# AFE_DIFF.net
KiCad netlist of a schematic drawn in Altium Designer
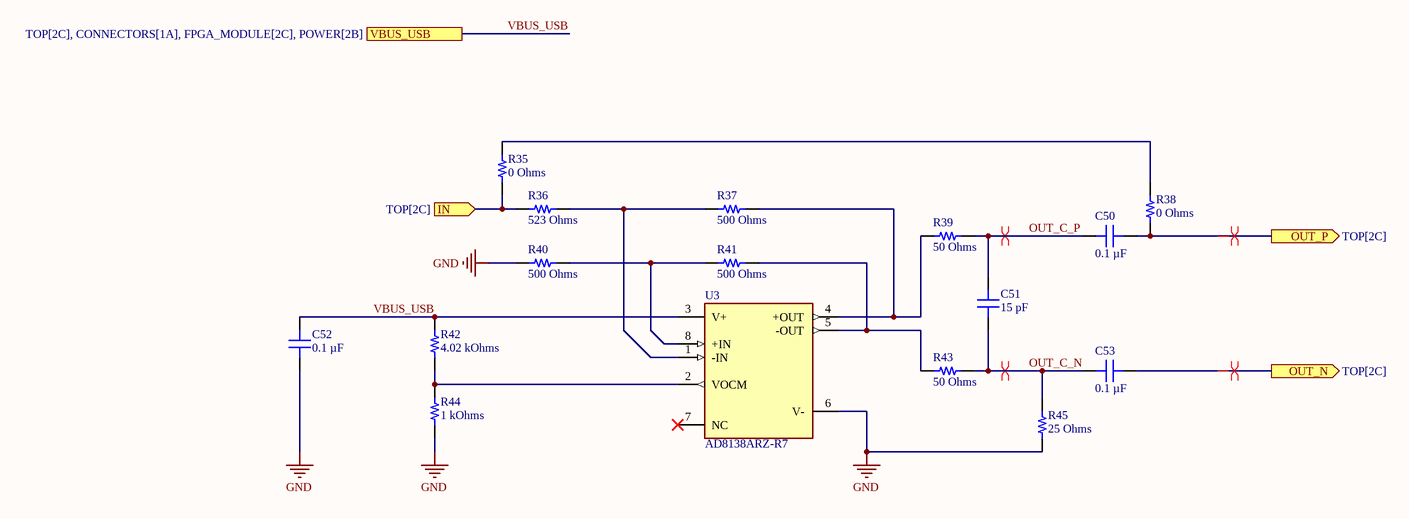
[diagram p0: AFE_DIFF.SchDoc]

(export (version "E")
  (design (tool "Eeschema 10.0.6"))
  (components
    (comp (ref "C50")
      (value "0.1 µF")
      (footprint "CAP 0402_1005")
      (description "CAP CER 0.1UF 50V X5R 0402")
      (fields
        (field (name "PART NUMBER") "CGA2B3X5R1H104M050BB")
        (field (name "MANUFACTURER") "TDK Corporation")
      )
      (libsource (lib "Celestial") (part "Capacitor"))
    )
    (comp (ref "C51")
      (value "15 pF")
      (footprint "CAP 0603_1608")
      (description "CAP CER 15PF 25V C0G/NP0 0603")
      (fields (field (name "PART NUMBER") "C0603C150J3GACAUTO") (field (name "MANUFACTURER") "KEMET"))
      (libsource (lib "Celestial") (part "Capacitor"))
    )
    (comp (ref "C52")
      (value "0.1 µF")
      (footprint "CAP 0402_1005")
      (description "CAP CER 0.1UF 50V X5R 0402")
      (fields
        (field (name "PART NUMBER") "CGA2B3X5R1H104M050BB")
        (field (name "MANUFACTURER") "TDK Corporation")
      )
      (libsource (lib "Celestial") (part "Capacitor"))
    )
    (comp (ref "C53")
      (value "0.1 µF")
      (footprint "CAP 0402_1005")
      (description "CAP CER 0.1UF 50V X5R 0402")
      (fields
        (field (name "PART NUMBER") "CGA2B3X5R1H104M050BB")
        (field (name "MANUFACTURER") "TDK Corporation")
      )
      (libsource (lib "Celestial") (part "Capacitor"))
    )
    (comp (ref "R35")
      (value "0 Ohms")
      (footprint "RES 0603_1608")
      (description "RES SMD 0 OHM JUMPER 1/2W 0603")
      (fields (field (name "PART NUMBER") "5110") (field (name "MANUFACTURER") "Keystone Electronics"))
      (libsource (lib "Celestial") (part "Resistor"))
    )
    (comp (ref "R36")
      (value "523 Ohms")
      (footprint "RES 0402_1005")
      (description "RES SMD 523 OHM 0.1% 1/16W 0402")
      (fields
        (field (name "PART NUMBER") "ERA-2ARB5230X")
        (field (name "MANUFACTURER") "Panasonic Electronic Components")
      )
      (libsource (lib "Celestial") (part "Resistor"))
    )
    (comp (ref "R37")
      (value "500 Ohms")
      (footprint "RES 0603_1608")
      (description "RES SMD 500 OHM 0.05% 1/10W 0603")
      (fields (field (name "PART NUMBER") "TNPU0603500RAZEN00") (field (name "MANUFACTURER") "Vishay Dale"))
      (libsource (lib "Celestial") (part "Resistor"))
    )
    (comp (ref "R38")
      (value "0 Ohms")
      (footprint "RES 0603_1608")
      (description "RES SMD 0 OHM JUMPER 1/2W 0603")
      (fields (field (name "PART NUMBER") "5110") (field (name "MANUFACTURER") "Keystone Electronics"))
      (libsource (lib "Celestial") (part "Resistor"))
    )
    (comp (ref "R39")
      (value "50 Ohms")
      (footprint "RES 0603_1608")
      (description "RES 50 OHM 5% 1/8W 0603")
      (fields (field (name "PART NUMBER") "CH0603-50RJNTA") (field (name "MANUFACTURER") "Vishay Sfernice"))
      (libsource (lib "Celestial") (part "Resistor"))
    )
    (comp (ref "R40")
      (value "500 Ohms")
      (footprint "RES 0603_1608")
      (description "RES SMD 500 OHM 0.05% 1/10W 0603")
      (fields (field (name "PART NUMBER") "TNPU0603500RAZEN00") (field (name "MANUFACTURER") "Vishay Dale"))
      (libsource (lib "Celestial") (part "Resistor"))
    )
    (comp (ref "R41")
      (value "500 Ohms")
      (footprint "RES 0603_1608")
      (description "RES SMD 500 OHM 0.05% 1/10W 0603")
      (fields (field (name "PART NUMBER") "TNPU0603500RAZEN00") (field (name "MANUFACTURER") "Vishay Dale"))
      (libsource (lib "Celestial") (part "Resistor"))
    )
    (comp (ref "R42")
      (value "4.02 kOhms")
      (footprint "RES 0603_1608")
      (description "RES SMD 4.02K OHM 1% 1/10W 0603")
      (fields (field (name "PART NUMBER") "AC0603FR-074K02L") (field (name "MANUFACTURER") "Yageo"))
      (libsource (lib "Celestial") (part "Resistor"))
    )
    (comp (ref "R43")
      (value "50 Ohms")
      (footprint "RES 0603_1608")
      (description "RES 50 OHM 5% 1/8W 0603")
      (fields (field (name "PART NUMBER") "CH0603-50RJNTA") (field (name "MANUFACTURER") "Vishay Sfernice"))
      (libsource (lib "Celestial") (part "Resistor"))
    )
    (comp (ref "R44")
      (value "1 kOhms")
      (footprint "RES 0603_1608")
      (description "RES SMD 1K OHM 1% 1/10W 0603")
      (fields (field (name "PART NUMBER") "AA0603FR-071KL") (field (name "MANUFACTURER") "Yageo"))
      (libsource (lib "Celestial") (part "Resistor"))
    )
    (comp (ref "R45")
      (value "25 Ohms")
      (footprint "RES 0402_1005")
      (description "RES 25 OHM 0.1% 1/20W 0402")
      (fields (field (name "PART NUMBER") "FC0402E25R0BST0") (field (name "MANUFACTURER") "Vishay Thin Film"))
      (libsource (lib "Celestial") (part "Resistor"))
    )
    (comp (ref "U3")
      (value "AD8138ARZ-R7")
      (footprint "FP-R-8-IPC_A")
      (description "IC ADC DRIVER 8SOIC")
      (libsource (lib "Altium Content Vault") (part "538c1b5816b8d819c8aa865c7aeb83c"))
    )
  )
  (nets
    (net (code "1") (name "/IN") (class "Default")
      (node (ref "R35") (pin "1") (pinfunction "1_1") (pintype "passive"))
      (node (ref "R36") (pin "1") (pinfunction "1_1") (pintype "passive"))
    )
    (net (code "2") (name "/OUT_C_N") (class "Default")
      (node (ref "C51") (pin "1") (pinfunction "1_1") (pintype "passive"))
      (node (ref "C53") (pin "2") (pinfunction "2_2") (pintype "passive"))
      (node (ref "R43") (pin "2") (pinfunction "2_2") (pintype "passive"))
      (node (ref "R45") (pin "2") (pinfunction "2_2") (pintype "passive"))
    )
    (net (code "3") (name "/OUT_C_P") (class "Default")
      (node (ref "C50") (pin "2") (pinfunction "2_2") (pintype "passive"))
      (node (ref "C51") (pin "2") (pinfunction "2_2") (pintype "passive"))
      (node (ref "R39") (pin "2") (pinfunction "2_2") (pintype "passive"))
    )
    (net (code "4") (name "/OUT_N") (class "Default")
      (node (ref "C53") (pin "1") (pinfunction "1_1") (pintype "passive"))
    )
    (net (code "5") (name "/OUT_P") (class "Default")
      (node (ref "C50") (pin "1") (pinfunction "1_1") (pintype "passive"))
      (node (ref "R38") (pin "1") (pinfunction "1_1") (pintype "passive"))
    )
    (net (code "6") (name "/VBUS_USB") (class "Default")
      (node (ref "C52") (pin "2") (pinfunction "2_2") (pintype "passive"))
      (node (ref "R42") (pin "2") (pinfunction "2_2") (pintype "passive"))
      (node (ref "U3") (pin "3") (pinfunction "V+_3") (pintype "power_in"))
    )
    (net (code "7") (name "GND") (class "Default")
      (node (ref "C52") (pin "1") (pinfunction "1_1") (pintype "passive"))
      (node (ref "R40") (pin "1") (pinfunction "1_1") (pintype "passive"))
      (node (ref "R44") (pin "1") (pinfunction "1_1") (pintype "passive"))
      (node (ref "R45") (pin "1") (pinfunction "1_1") (pintype "passive"))
      (node (ref "U3") (pin "6") (pinfunction "V-_6") (pintype "power_in"))
    )
    (net (code "8") (name "Net-(R35-Pad2)") (class "Default")
      (node (ref "R35") (pin "2") (pinfunction "2_2") (pintype "passive"))
      (node (ref "R38") (pin "2") (pinfunction "2_2") (pintype "passive"))
    )
    (net (code "9") (name "Net-(U3-+IN)") (class "Default")
      (node (ref "R40") (pin "2") (pinfunction "2_2") (pintype "passive"))
      (node (ref "R41") (pin "1") (pinfunction "1_1") (pintype "passive"))
      (node (ref "U3") (pin "8") (pinfunction "+IN_8") (pintype "input"))
    )
    (net (code "10") (name "Net-(U3-+OUT)") (class "Default")
      (node (ref "R37") (pin "2") (pinfunction "2_2") (pintype "passive"))
      (node (ref "R39") (pin "1") (pinfunction "1_1") (pintype "passive"))
      (node (ref "U3") (pin "4") (pinfunction "+OUT_4") (pintype "output"))
    )
    (net (code "11") (name "Net-(U3--IN)") (class "Default")
      (node (ref "R36") (pin "2") (pinfunction "2_2") (pintype "passive"))
      (node (ref "R37") (pin "1") (pinfunction "1_1") (pintype "passive"))
      (node (ref "U3") (pin "1") (pinfunction "-IN_1") (pintype "input"))
    )
    (net (code "12") (name "Net-(U3--OUT)") (class "Default")
      (node (ref "R41") (pin "2") (pinfunction "2_2") (pintype "passive"))
      (node (ref "R43") (pin "1") (pinfunction "1_1") (pintype "passive"))
      (node (ref "U3") (pin "5") (pinfunction "-OUT_5") (pintype "output"))
    )
    (net (code "13") (name "Net-(U3-VOCM)") (class "Default")
      (node (ref "R42") (pin "1") (pinfunction "1_1") (pintype "passive"))
      (node (ref "R44") (pin "2") (pinfunction "2_2") (pintype "passive"))
      (node (ref "U3") (pin "2") (pinfunction "VOCM_2") (pintype "output"))
    )
    (net (code "14") (name "unconnected-(U3-NC-Pad7)") (class "Default")
      (node (ref "U3") (pin "7") (pinfunction "NC_7") (pintype "passive+no_connect"))
    )
  )
)
